# LEDs.net
KiCad netlist of a schematic drawn in Altium Designer
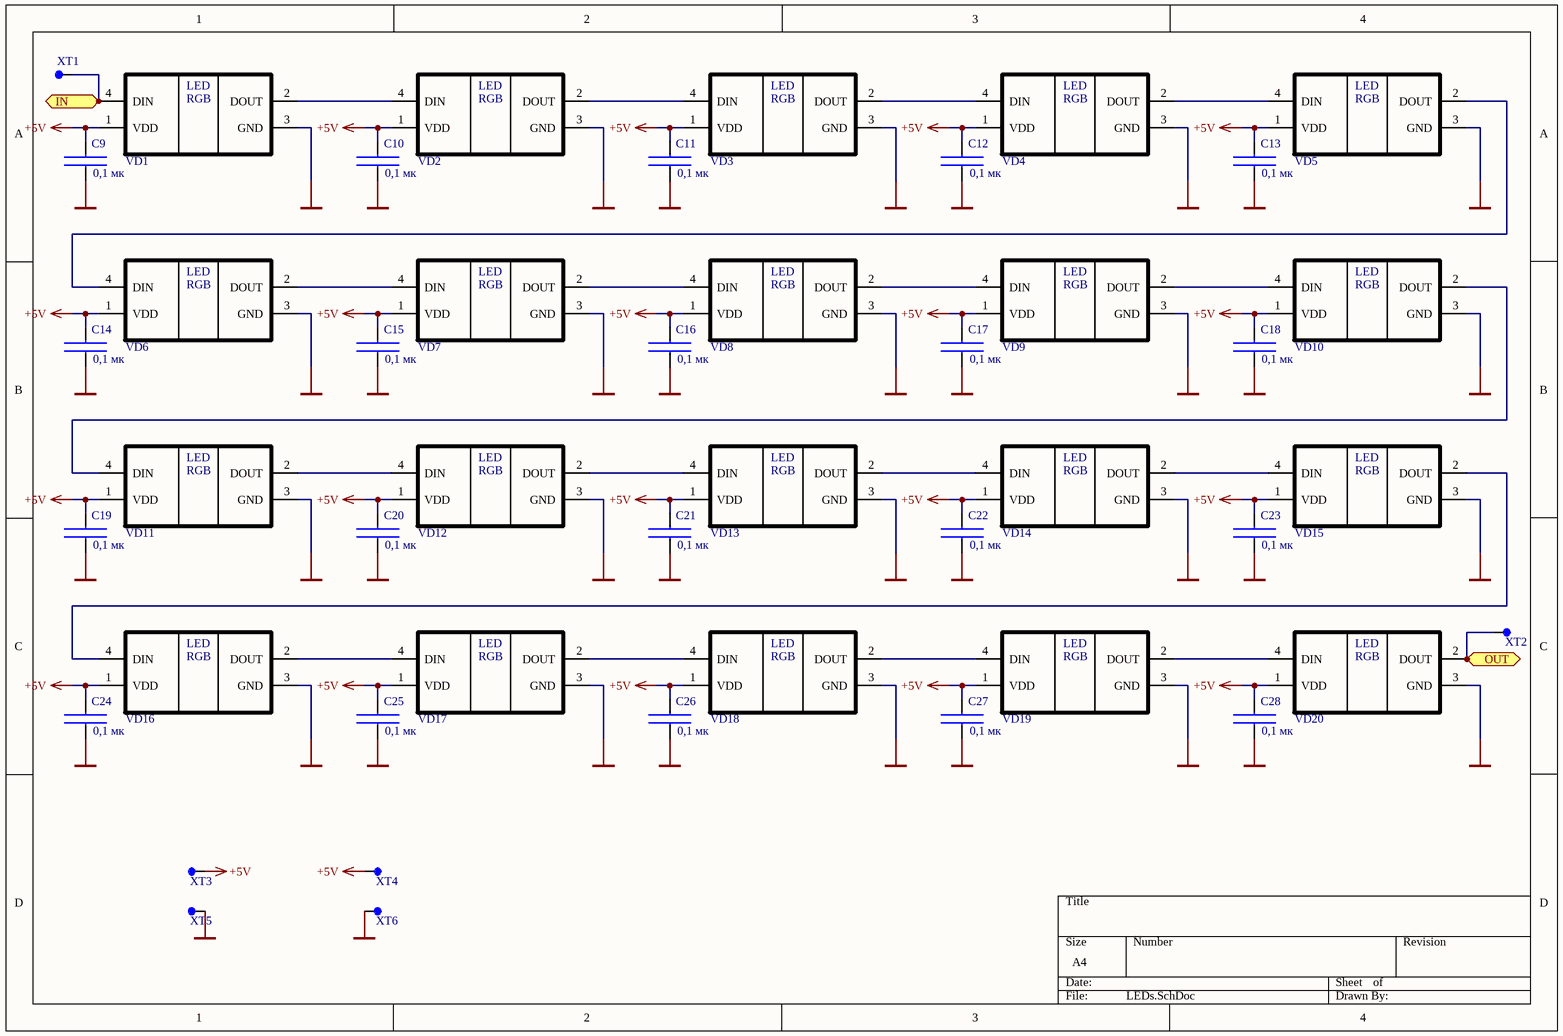
[diagram p0: LEDs.SchDoc]

(export (version "E")
  (design (tool "Eeschema 10.0.6"))
  (components
    (comp (ref "C9")
      (value "0,1 мк")
      (footprint "CC1608(0603)x09")
      (description "Ceramic Chip-capacitor 0603")
      (fields (field (name "VOLTAGE") "25 / 16"))
      (libsource (lib "PCB_Project1_6") (part "CC0603 X7R uF0.22 V25/16"))
    )
    (comp (ref "C10")
      (value "0,1 мк")
      (footprint "CC1608(0603)x09")
      (description "Ceramic Chip-capacitor 0603")
      (fields (field (name "VOLTAGE") "25 / 16"))
      (libsource (lib "PCB_Project1_6") (part "CC0603 X7R uF0.22 V25/16"))
    )
    (comp (ref "C11")
      (value "0,1 мк")
      (footprint "CC1608(0603)x09")
      (description "Ceramic Chip-capacitor 0603")
      (fields (field (name "VOLTAGE") "25 / 16"))
      (libsource (lib "PCB_Project1_6") (part "CC0603 X7R uF0.22 V25/16"))
    )
    (comp (ref "C12")
      (value "0,1 мк")
      (footprint "CC1608(0603)x09")
      (description "Ceramic Chip-capacitor 0603")
      (fields (field (name "VOLTAGE") "25 / 16"))
      (libsource (lib "PCB_Project1_6") (part "CC0603 X7R uF0.22 V25/16"))
    )
    (comp (ref "C13")
      (value "0,1 мк")
      (footprint "CC1608(0603)x09")
      (description "Ceramic Chip-capacitor 0603")
      (fields (field (name "VOLTAGE") "25 / 16"))
      (libsource (lib "PCB_Project1_6") (part "CC0603 X7R uF0.22 V25/16"))
    )
    (comp (ref "C14")
      (value "0,1 мк")
      (footprint "CC1608(0603)x09")
      (description "Ceramic Chip-capacitor 0603")
      (fields (field (name "VOLTAGE") "25 / 16"))
      (libsource (lib "PCB_Project1_6") (part "CC0603 X7R uF0.22 V25/16"))
    )
    (comp (ref "C15")
      (value "0,1 мк")
      (footprint "CC1608(0603)x09")
      (description "Ceramic Chip-capacitor 0603")
      (fields (field (name "VOLTAGE") "25 / 16"))
      (libsource (lib "PCB_Project1_6") (part "CC0603 X7R uF0.22 V25/16"))
    )
    (comp (ref "C16")
      (value "0,1 мк")
      (footprint "CC1608(0603)x09")
      (description "Ceramic Chip-capacitor 0603")
      (fields (field (name "VOLTAGE") "25 / 16"))
      (libsource (lib "PCB_Project1_6") (part "CC0603 X7R uF0.22 V25/16"))
    )
    (comp (ref "C17")
      (value "0,1 мк")
      (footprint "CC1608(0603)x09")
      (description "Ceramic Chip-capacitor 0603")
      (fields (field (name "VOLTAGE") "25 / 16"))
      (libsource (lib "PCB_Project1_6") (part "CC0603 X7R uF0.22 V25/16"))
    )
    (comp (ref "C18")
      (value "0,1 мк")
      (footprint "CC1608(0603)x09")
      (description "Ceramic Chip-capacitor 0603")
      (fields (field (name "VOLTAGE") "25 / 16"))
      (libsource (lib "PCB_Project1_6") (part "CC0603 X7R uF0.22 V25/16"))
    )
    (comp (ref "C19")
      (value "0,1 мк")
      (footprint "CC1608(0603)x09")
      (description "Ceramic Chip-capacitor 0603")
      (fields (field (name "VOLTAGE") "25 / 16"))
      (libsource (lib "PCB_Project1_6") (part "CC0603 X7R uF0.22 V25/16"))
    )
    (comp (ref "C20")
      (value "0,1 мк")
      (footprint "CC1608(0603)x09")
      (description "Ceramic Chip-capacitor 0603")
      (fields (field (name "VOLTAGE") "25 / 16"))
      (libsource (lib "PCB_Project1_6") (part "CC0603 X7R uF0.22 V25/16"))
    )
    (comp (ref "C21")
      (value "0,1 мк")
      (footprint "CC1608(0603)x09")
      (description "Ceramic Chip-capacitor 0603")
      (fields (field (name "VOLTAGE") "25 / 16"))
      (libsource (lib "PCB_Project1_6") (part "CC0603 X7R uF0.22 V25/16"))
    )
    (comp (ref "C22")
      (value "0,1 мк")
      (footprint "CC1608(0603)x09")
      (description "Ceramic Chip-capacitor 0603")
      (fields (field (name "VOLTAGE") "25 / 16"))
      (libsource (lib "PCB_Project1_6") (part "CC0603 X7R uF0.22 V25/16"))
    )
    (comp (ref "C23")
      (value "0,1 мк")
      (footprint "CC1608(0603)x09")
      (description "Ceramic Chip-capacitor 0603")
      (fields (field (name "VOLTAGE") "25 / 16"))
      (libsource (lib "PCB_Project1_6") (part "CC0603 X7R uF0.22 V25/16"))
    )
    (comp (ref "C24")
      (value "0,1 мк")
      (footprint "CC1608(0603)x09")
      (description "Ceramic Chip-capacitor 0603")
      (fields (field (name "VOLTAGE") "25 / 16"))
      (libsource (lib "PCB_Project1_6") (part "CC0603 X7R uF0.22 V25/16"))
    )
    (comp (ref "C25")
      (value "0,1 мк")
      (footprint "CC1608(0603)x09")
      (description "Ceramic Chip-capacitor 0603")
      (fields (field (name "VOLTAGE") "25 / 16"))
      (libsource (lib "PCB_Project1_6") (part "CC0603 X7R uF0.22 V25/16"))
    )
    (comp (ref "C26")
      (value "0,1 мк")
      (footprint "CC1608(0603)x09")
      (description "Ceramic Chip-capacitor 0603")
      (fields (field (name "VOLTAGE") "25 / 16"))
      (libsource (lib "PCB_Project1_6") (part "CC0603 X7R uF0.22 V25/16"))
    )
    (comp (ref "C27")
      (value "0,1 мк")
      (footprint "CC1608(0603)x09")
      (description "Ceramic Chip-capacitor 0603")
      (fields (field (name "VOLTAGE") "25 / 16"))
      (libsource (lib "PCB_Project1_6") (part "CC0603 X7R uF0.22 V25/16"))
    )
    (comp (ref "C28")
      (value "0,1 мк")
      (footprint "CC1608(0603)x09")
      (description "Ceramic Chip-capacitor 0603")
      (fields (field (name "VOLTAGE") "25 / 16"))
      (libsource (lib "PCB_Project1_6") (part "CC0603 X7R uF0.22 V25/16"))
    )
    (comp (ref "VD1") (value "W2812B") (footprint "WS2812B") (libsource (lib "clock2") (part "W2812B")))
    (comp (ref "VD2") (value "W2812B") (footprint "WS2812B") (libsource (lib "clock2") (part "W2812B")))
    (comp (ref "VD3") (value "W2812B") (footprint "WS2812B") (libsource (lib "clock2") (part "W2812B")))
    (comp (ref "VD4") (value "W2812B") (footprint "WS2812B") (libsource (lib "clock2") (part "W2812B")))
    (comp (ref "VD5") (value "W2812B") (footprint "WS2812B") (libsource (lib "clock2") (part "W2812B")))
    (comp (ref "VD6") (value "W2812B") (footprint "WS2812B") (libsource (lib "clock2") (part "W2812B")))
    (comp (ref "VD7") (value "W2812B") (footprint "WS2812B") (libsource (lib "clock2") (part "W2812B")))
    (comp (ref "VD8") (value "W2812B") (footprint "WS2812B") (libsource (lib "clock2") (part "W2812B")))
    (comp (ref "VD9") (value "W2812B") (footprint "WS2812B") (libsource (lib "clock2") (part "W2812B")))
    (comp (ref "VD10") (value "W2812B") (footprint "WS2812B") (libsource (lib "clock2") (part "W2812B")))
    (comp (ref "VD11") (value "W2812B") (footprint "WS2812B") (libsource (lib "clock2") (part "W2812B")))
    (comp (ref "VD12") (value "W2812B") (footprint "WS2812B") (libsource (lib "clock2") (part "W2812B")))
    (comp (ref "VD13") (value "W2812B") (footprint "WS2812B") (libsource (lib "clock2") (part "W2812B")))
    (comp (ref "VD14") (value "W2812B") (footprint "WS2812B") (libsource (lib "clock2") (part "W2812B")))
    (comp (ref "VD15") (value "W2812B") (footprint "WS2812B") (libsource (lib "clock2") (part "W2812B")))
    (comp (ref "VD16") (value "W2812B") (footprint "WS2812B") (libsource (lib "clock2") (part "W2812B")))
    (comp (ref "VD17") (value "W2812B") (footprint "WS2812B") (libsource (lib "clock2") (part "W2812B")))
    (comp (ref "VD18") (value "W2812B") (footprint "WS2812B") (libsource (lib "clock2") (part "W2812B")))
    (comp (ref "VD19") (value "W2812B") (footprint "WS2812B") (libsource (lib "clock2") (part "W2812B")))
    (comp (ref "VD20") (value "W2812B") (footprint "WS2812B") (libsource (lib "clock2") (part "W2812B")))
    (comp (ref "XT1") (value "XT3") (footprint "XT3") (libsource (lib "clock2") (part "XT3")))
    (comp (ref "XT2") (value "XT3") (footprint "XT3") (libsource (lib "clock2") (part "XT3")))
    (comp (ref "XT3") (value "XT3") (footprint "XT3") (libsource (lib "clock2") (part "XT3")))
    (comp (ref "XT4") (value "XT3") (footprint "XT3") (libsource (lib "clock2") (part "XT3")))
    (comp (ref "XT5") (value "XT3") (footprint "XT3") (libsource (lib "clock2") (part "XT3")))
    (comp (ref "XT6") (value "XT3") (footprint "XT3") (libsource (lib "clock2") (part "XT3")))
  )
  (nets
    (net (code "1") (name "+5V") (class "Default")
      (node (ref "C10") (pin "1") (pintype "passive"))
      (node (ref "C11") (pin "1") (pintype "passive"))
      (node (ref "C12") (pin "1") (pintype "passive"))
      (node (ref "C13") (pin "1") (pintype "passive"))
      (node (ref "C14") (pin "1") (pintype "passive"))
      (node (ref "C15") (pin "1") (pintype "passive"))
      (node (ref "C16") (pin "1") (pintype "passive"))
      (node (ref "C17") (pin "1") (pintype "passive"))
      (node (ref "C18") (pin "1") (pintype "passive"))
      (node (ref "C19") (pin "1") (pintype "passive"))
      (node (ref "C20") (pin "1") (pintype "passive"))
      (node (ref "C21") (pin "1") (pintype "passive"))
      (node (ref "C22") (pin "1") (pintype "passive"))
      (node (ref "C23") (pin "1") (pintype "passive"))
      (node (ref "C24") (pin "1") (pintype "passive"))
      (node (ref "C25") (pin "1") (pintype "passive"))
      (node (ref "C26") (pin "1") (pintype "passive"))
      (node (ref "C27") (pin "1") (pintype "passive"))
      (node (ref "C28") (pin "1") (pintype "passive"))
      (node (ref "C9") (pin "1") (pintype "passive"))
      (node (ref "VD1") (pin "1") (pinfunction "VDD_1") (pintype "passive"))
      (node (ref "VD10") (pin "1") (pinfunction "VDD_1") (pintype "passive"))
      (node (ref "VD11") (pin "1") (pinfunction "VDD_1") (pintype "passive"))
      (node (ref "VD12") (pin "1") (pinfunction "VDD_1") (pintype "passive"))
      (node (ref "VD13") (pin "1") (pinfunction "VDD_1") (pintype "passive"))
      (node (ref "VD14") (pin "1") (pinfunction "VDD_1") (pintype "passive"))
      (node (ref "VD15") (pin "1") (pinfunction "VDD_1") (pintype "passive"))
      (node (ref "VD16") (pin "1") (pinfunction "VDD_1") (pintype "passive"))
      (node (ref "VD17") (pin "1") (pinfunction "VDD_1") (pintype "passive"))
      (node (ref "VD18") (pin "1") (pinfunction "VDD_1") (pintype "passive"))
      (node (ref "VD19") (pin "1") (pinfunction "VDD_1") (pintype "passive"))
      (node (ref "VD2") (pin "1") (pinfunction "VDD_1") (pintype "passive"))
      (node (ref "VD20") (pin "1") (pinfunction "VDD_1") (pintype "passive"))
      (node (ref "VD3") (pin "1") (pinfunction "VDD_1") (pintype "passive"))
      (node (ref "VD4") (pin "1") (pinfunction "VDD_1") (pintype "passive"))
      (node (ref "VD5") (pin "1") (pinfunction "VDD_1") (pintype "passive"))
      (node (ref "VD6") (pin "1") (pinfunction "VDD_1") (pintype "passive"))
      (node (ref "VD7") (pin "1") (pinfunction "VDD_1") (pintype "passive"))
      (node (ref "VD8") (pin "1") (pinfunction "VDD_1") (pintype "passive"))
      (node (ref "VD9") (pin "1") (pinfunction "VDD_1") (pintype "passive"))
      (node (ref "XT3") (pin "1") (pintype "passive"))
      (node (ref "XT4") (pin "1") (pintype "passive"))
    )
    (net (code "2") (name "/IN") (class "Default")
      (node (ref "VD1") (pin "4") (pinfunction "DIN_4") (pintype "passive"))
      (node (ref "XT1") (pin "1") (pintype "passive"))
    )
    (net (code "3") (name "/OUT") (class "Default")
      (node (ref "VD20") (pin "2") (pinfunction "DOUT_2") (pintype "passive"))
      (node (ref "XT2") (pin "1") (pintype "passive"))
    )
    (net (code "4") (name "GND") (class "Default")
      (node (ref "C10") (pin "2") (pintype "passive"))
      (node (ref "C11") (pin "2") (pintype "passive"))
      (node (ref "C12") (pin "2") (pintype "passive"))
      (node (ref "C13") (pin "2") (pintype "passive"))
      (node (ref "C14") (pin "2") (pintype "passive"))
      (node (ref "C15") (pin "2") (pintype "passive"))
      (node (ref "C16") (pin "2") (pintype "passive"))
      (node (ref "C17") (pin "2") (pintype "passive"))
      (node (ref "C18") (pin "2") (pintype "passive"))
      (node (ref "C19") (pin "2") (pintype "passive"))
      (node (ref "C20") (pin "2") (pintype "passive"))
      (node (ref "C21") (pin "2") (pintype "passive"))
      (node (ref "C22") (pin "2") (pintype "passive"))
      (node (ref "C23") (pin "2") (pintype "passive"))
      (node (ref "C24") (pin "2") (pintype "passive"))
      (node (ref "C25") (pin "2") (pintype "passive"))
      (node (ref "C26") (pin "2") (pintype "passive"))
      (node (ref "C27") (pin "2") (pintype "passive"))
      (node (ref "C28") (pin "2") (pintype "passive"))
      (node (ref "C9") (pin "2") (pintype "passive"))
      (node (ref "VD1") (pin "3") (pinfunction "GND_3") (pintype "passive"))
      (node (ref "VD10") (pin "3") (pinfunction "GND_3") (pintype "passive"))
      (node (ref "VD11") (pin "3") (pinfunction "GND_3") (pintype "passive"))
      (node (ref "VD12") (pin "3") (pinfunction "GND_3") (pintype "passive"))
      (node (ref "VD13") (pin "3") (pinfunction "GND_3") (pintype "passive"))
      (node (ref "VD14") (pin "3") (pinfunction "GND_3") (pintype "passive"))
      (node (ref "VD15") (pin "3") (pinfunction "GND_3") (pintype "passive"))
      (node (ref "VD16") (pin "3") (pinfunction "GND_3") (pintype "passive"))
      (node (ref "VD17") (pin "3") (pinfunction "GND_3") (pintype "passive"))
      (node (ref "VD18") (pin "3") (pinfunction "GND_3") (pintype "passive"))
      (node (ref "VD19") (pin "3") (pinfunction "GND_3") (pintype "passive"))
      (node (ref "VD2") (pin "3") (pinfunction "GND_3") (pintype "passive"))
      (node (ref "VD20") (pin "3") (pinfunction "GND_3") (pintype "passive"))
      (node (ref "VD3") (pin "3") (pinfunction "GND_3") (pintype "passive"))
      (node (ref "VD4") (pin "3") (pinfunction "GND_3") (pintype "passive"))
      (node (ref "VD5") (pin "3") (pinfunction "GND_3") (pintype "passive"))
      (node (ref "VD6") (pin "3") (pinfunction "GND_3") (pintype "passive"))
      (node (ref "VD7") (pin "3") (pinfunction "GND_3") (pintype "passive"))
      (node (ref "VD8") (pin "3") (pinfunction "GND_3") (pintype "passive"))
      (node (ref "VD9") (pin "3") (pinfunction "GND_3") (pintype "passive"))
      (node (ref "XT5") (pin "1") (pintype "passive"))
      (node (ref "XT6") (pin "1") (pintype "passive"))
    )
    (net (code "5") (name "Net-(VD1-DOUT)") (class "Default")
      (node (ref "VD1") (pin "2") (pinfunction "DOUT_2") (pintype "passive"))
      (node (ref "VD2") (pin "4") (pinfunction "DIN_4") (pintype "passive"))
    )
    (net (code "6") (name "Net-(VD2-DOUT)") (class "Default")
      (node (ref "VD2") (pin "2") (pinfunction "DOUT_2") (pintype "passive"))
      (node (ref "VD3") (pin "4") (pinfunction "DIN_4") (pintype "passive"))
    )
    (net (code "7") (name "Net-(VD3-DOUT)") (class "Default")
      (node (ref "VD3") (pin "2") (pinfunction "DOUT_2") (pintype "passive"))
      (node (ref "VD4") (pin "4") (pinfunction "DIN_4") (pintype "passive"))
    )
    (net (code "8") (name "Net-(VD4-DOUT)") (class "Default")
      (node (ref "VD4") (pin "2") (pinfunction "DOUT_2") (pintype "passive"))
      (node (ref "VD5") (pin "4") (pinfunction "DIN_4") (pintype "passive"))
    )
    (net (code "9") (name "Net-(VD5-DOUT)") (class "Default")
      (node (ref "VD5") (pin "2") (pinfunction "DOUT_2") (pintype "passive"))
      (node (ref "VD6") (pin "4") (pinfunction "DIN_4") (pintype "passive"))
    )
    (net (code "10") (name "Net-(VD6-DOUT)") (class "Default")
      (node (ref "VD6") (pin "2") (pinfunction "DOUT_2") (pintype "passive"))
      (node (ref "VD7") (pin "4") (pinfunction "DIN_4") (pintype "passive"))
    )
    (net (code "11") (name "Net-(VD7-DOUT)") (class "Default")
      (node (ref "VD7") (pin "2") (pinfunction "DOUT_2") (pintype "passive"))
      (node (ref "VD8") (pin "4") (pinfunction "DIN_4") (pintype "passive"))
    )
    (net (code "12") (name "Net-(VD8-DOUT)") (class "Default")
      (node (ref "VD8") (pin "2") (pinfunction "DOUT_2") (pintype "passive"))
      (node (ref "VD9") (pin "4") (pinfunction "DIN_4") (pintype "passive"))
    )
    (net (code "13") (name "Net-(VD10-DIN)") (class "Default")
      (node (ref "VD10") (pin "4") (pinfunction "DIN_4") (pintype "passive"))
      (node (ref "VD9") (pin "2") (pinfunction "DOUT_2") (pintype "passive"))
    )
    (net (code "14") (name "Net-(VD10-DOUT)") (class "Default")
      (node (ref "VD10") (pin "2") (pinfunction "DOUT_2") (pintype "passive"))
      (node (ref "VD11") (pin "4") (pinfunction "DIN_4") (pintype "passive"))
    )
    (net (code "15") (name "Net-(VD11-DOUT)") (class "Default")
      (node (ref "VD11") (pin "2") (pinfunction "DOUT_2") (pintype "passive"))
      (node (ref "VD12") (pin "4") (pinfunction "DIN_4") (pintype "passive"))
    )
    (net (code "16") (name "Net-(VD12-DOUT)") (class "Default")
      (node (ref "VD12") (pin "2") (pinfunction "DOUT_2") (pintype "passive"))
      (node (ref "VD13") (pin "4") (pinfunction "DIN_4") (pintype "passive"))
    )
    (net (code "17") (name "Net-(VD13-DOUT)") (class "Default")
      (node (ref "VD13") (pin "2") (pinfunction "DOUT_2") (pintype "passive"))
      (node (ref "VD14") (pin "4") (pinfunction "DIN_4") (pintype "passive"))
    )
    (net (code "18") (name "Net-(VD14-DOUT)") (class "Default")
      (node (ref "VD14") (pin "2") (pinfunction "DOUT_2") (pintype "passive"))
      (node (ref "VD15") (pin "4") (pinfunction "DIN_4") (pintype "passive"))
    )
    (net (code "19") (name "Net-(VD15-DOUT)") (class "Default")
      (node (ref "VD15") (pin "2") (pinfunction "DOUT_2") (pintype "passive"))
      (node (ref "VD16") (pin "4") (pinfunction "DIN_4") (pintype "passive"))
    )
    (net (code "20") (name "Net-(VD16-DOUT)") (class "Default")
      (node (ref "VD16") (pin "2") (pinfunction "DOUT_2") (pintype "passive"))
      (node (ref "VD17") (pin "4") (pinfunction "DIN_4") (pintype "passive"))
    )
    (net (code "21") (name "Net-(VD17-DOUT)") (class "Default")
      (node (ref "VD17") (pin "2") (pinfunction "DOUT_2") (pintype "passive"))
      (node (ref "VD18") (pin "4") (pinfunction "DIN_4") (pintype "passive"))
    )
    (net (code "22") (name "Net-(VD18-DOUT)") (class "Default")
      (node (ref "VD18") (pin "2") (pinfunction "DOUT_2") (pintype "passive"))
      (node (ref "VD19") (pin "4") (pinfunction "DIN_4") (pintype "passive"))
    )
    (net (code "23") (name "Net-(VD19-DOUT)") (class "Default")
      (node (ref "VD19") (pin "2") (pinfunction "DOUT_2") (pintype "passive"))
      (node (ref "VD20") (pin "4") (pinfunction "DIN_4") (pintype "passive"))
    )
  )
)
